# BrightnessControl.net
KiCad netlist of a schematic drawn in Altium Designer
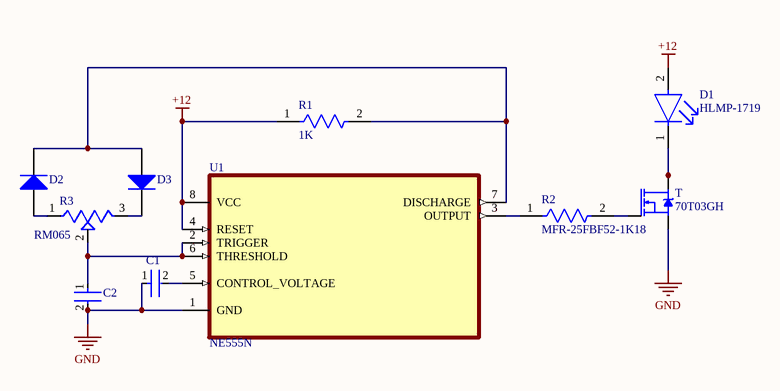
[diagram p0: BrightnessControl.SchDoc]

(export (version "E")
  (design (tool "Eeschema 10.0.6"))
  (components
    (comp (ref "C1")
      (value "CL21A335KPFNNNG")
      (footprint "FP-CL21-IPC_A")
      (description "CL21 Series 0805 3.3uF 10V ±10% Tolerance X5R Multilayer Ceramic Chip Capacitor")
      (fields (field (name "TOLERANCE") "10%"))
      (libsource (lib "Altium Content Vault") (part "b4654b650e69147ec39a6b967a45e02"))
    )
    (comp (ref "C2")
      (value "CL21A335KPFNNNG")
      (footprint "FP-CL21-IPC_A")
      (description "CL21 Series 0805 3.3uF 10V ±10% Tolerance X5R Multilayer Ceramic Chip Capacitor")
      (fields (field (name "TOLERANCE") "10%"))
      (libsource (lib "Altium Content Vault") (part "b4654b650e69147ec39a6b967a45e02"))
    )
    (comp (ref "D1")
      (value "HLMP-1719")
      (footprint "FP-HLMP-1719-MFG")
      (description "LED YELLOW DIFFUSED T-1 T/H")
      (fields
        (field (name "MANUFACTURER") "Broadcom")
        (field (name "OCTOPART") "https://octopart.com/hlmp-1719-broadcom-71130405")
      )
      (libsource (lib "Altium Content Vault") (part "8706943c75ba83719d021d2fdc84c58"))
    )
    (comp (ref "D2")
      (value "1N4148")
      (footprint "NXP-SOD27-2_V")
      (description "High-speed Diode, 100 V, 450 mA, 2-Pin SOD27, RoHS")
      (fields (field (name "MANUFACTURER") "NXP Semiconductors"))
      (libsource (lib "Altium Content Vault") (part "NXP-A1K2-2"))
    )
    (comp (ref "D3")
      (value "1N4148")
      (footprint "NXP-SOD27-2_V")
      (description "High-speed Diode, 100 V, 450 mA, 2-Pin SOD27, RoHS")
      (fields (field (name "MANUFACTURER") "NXP Semiconductors"))
      (libsource (lib "Altium Content Vault") (part "NXP-A1K2-2"))
    )
    (comp (ref "R1")
      (value "1K")
      (footprint "FP-MFR-25-MFG")
      (description "RES 1.18K OHM 1/4W 1% AXIAL")
      (fields (field (name "MANUFACTURER") "Yageo") (field (name "TOLERANCE") "1%"))
      (libsource (lib "Altium Content Vault") (part "1029c3af85768c4190bb7ad29bc67b5"))
    )
    (comp (ref "R2")
      (value "MFR-25FBF52-1K18")
      (footprint "FP-MFR-25-MFG")
      (description "RES 1.18K OHM 1/4W 1% AXIAL")
      (fields (field (name "MANUFACTURER") "Yageo") (field (name "TOLERANCE") "1%"))
      (libsource (lib "Altium Content Vault") (part "1029c3af85768c4190bb7ad29bc67b5"))
    )
    (comp (ref "R3")
      (value "RM065")
      (footprint "RM065")
      (description "5 kOhms 0.1W, 1/10W PC Pins Through Hole Trimmer Potentiometer Carbon 1 Turn Top Adjustment")
      (fields (field (name "MF") "Bourns Inc.") (field (name "MP") "3318F-1-502"))
      (libsource (lib "Schlib1") (part "RM065"))
    )
    (comp (ref "T")
      (value "70T03GH")
      (footprint "TO252-3")
      (fields (field (name "MP") "IRLR2905TRPBF") (field (name "MF") "Infineon Technologies"))
      (libsource (lib "Schlib1") (part "70T03GH"))
    )
    (comp (ref "U1")
      (value "NE555N")
      (footprint "DIP8")
      (description "555 Type, Timer/Oscillator _Single_ IC 8-DIP")
      (fields (field (name "MF") "ON Semiconductor"))
      (libsource (lib "Schlib1") (part "NE555N"))
    )
  )
  (nets
    (net (code "1") (name "+12") (class "Default")
      (node (ref "D1") (pin "2") (pinfunction "A_2") (pintype "passive"))
      (node (ref "R1") (pin "1") (pinfunction "1_1") (pintype "passive"))
      (node (ref "U1") (pin "4") (pinfunction "RESET_4") (pintype "input"))
      (node (ref "U1") (pin "8") (pinfunction "VCC_8") (pintype "power_in"))
    )
    (net (code "2") (name "GND") (class "Default")
      (node (ref "C1") (pin "1") (pinfunction "1_1") (pintype "passive"))
      (node (ref "C2") (pin "2") (pinfunction "2_2") (pintype "passive"))
      (node (ref "T") (pin "3") (pinfunction "S_3") (pintype "bidirectional"))
      (node (ref "U1") (pin "1") (pinfunction "GND_1") (pintype "passive"))
    )
    (net (code "3") (name "Net-(D1-C)") (class "Default")
      (node (ref "D1") (pin "1") (pinfunction "C_1") (pintype "passive"))
      (node (ref "T") (pin "2") (pinfunction "D_2") (pintype "bidirectional"))
      (node (ref "T") (pin "PAD") (pinfunction "D_PAD") (pintype "bidirectional"))
    )
    (net (code "4") (name "Net-(D2-A)") (class "Default")
      (node (ref "D2") (pin "1") (pinfunction "A_1") (pintype "passive"))
      (node (ref "R3") (pin "1") (pinfunction "CCW_1") (pintype "passive"))
    )
    (net (code "5") (name "Net-(D2-K)") (class "Default")
      (node (ref "D2") (pin "2") (pinfunction "K_2") (pintype "passive"))
      (node (ref "D3") (pin "1") (pinfunction "A_1") (pintype "passive"))
      (node (ref "R1") (pin "2") (pinfunction "2_2") (pintype "passive"))
      (node (ref "U1") (pin "7") (pinfunction "DISCHARGE_7") (pintype "output"))
    )
    (net (code "6") (name "Net-(D3-K)") (class "Default")
      (node (ref "D3") (pin "2") (pinfunction "K_2") (pintype "passive"))
      (node (ref "R3") (pin "3") (pinfunction "CW_3") (pintype "passive"))
    )
    (net (code "7") (name "Net-(R3-WIPER)") (class "Default")
      (node (ref "C2") (pin "1") (pinfunction "1_1") (pintype "passive"))
      (node (ref "R3") (pin "2") (pinfunction "WIPER_2") (pintype "passive"))
      (node (ref "U1") (pin "2") (pinfunction "TRIGGER_2") (pintype "input"))
      (node (ref "U1") (pin "6") (pinfunction "THRESHOLD_6") (pintype "input"))
    )
    (net (code "8") (name "Net-(T-G)") (class "Default")
      (node (ref "R2") (pin "2") (pinfunction "2_2") (pintype "passive"))
      (node (ref "T") (pin "1") (pinfunction "G_1") (pintype "bidirectional"))
    )
    (net (code "9") (name "Net-(U1-CONTROL_VOLTAGE)") (class "Default")
      (node (ref "C1") (pin "2") (pinfunction "2_2") (pintype "passive"))
      (node (ref "U1") (pin "5") (pinfunction "CONTROL_VOLTAGE_5") (pintype "input"))
    )
    (net (code "10") (name "Net-(U1-OUTPUT)") (class "Default")
      (node (ref "R2") (pin "1") (pinfunction "1_1") (pintype "passive"))
      (node (ref "U1") (pin "3") (pinfunction "OUTPUT_3") (pintype "output"))
    )
  )
)
